# Sheet.net
KiCad netlist of a schematic drawn in Altium Designer
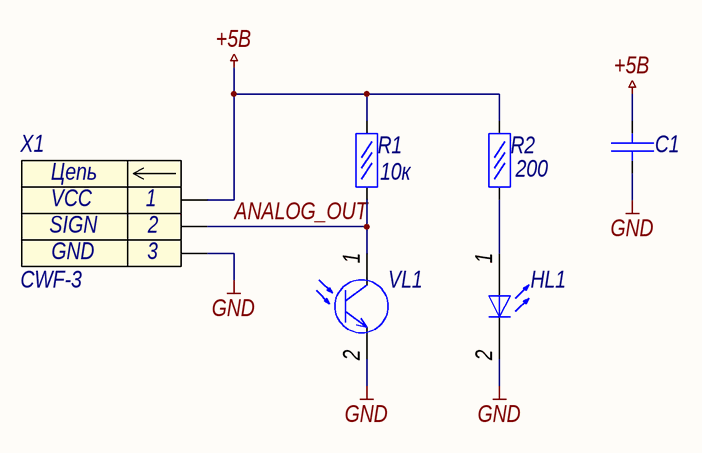
[diagram p0: Sheet.SchDoc]

(export (version "E")
  (design (tool "Eeschema 10.0.6"))
  (components
    (comp (ref "C1")
      (value "~")
      (footprint "C0805_AA")
      (description "Конденсатор кер.")
      (libsource (lib "mylib") (part "Конденсатор кер."))
    )
    (comp (ref "HL1") (value "~") (footprint "PCBComponent_2") (libsource (lib "mylib") (part "IR LED")))
    (comp (ref "R1")
      (value "10к")
      (footprint "R1206")
      (description "Резистор 0,05Вт")
      (libsource (lib "mylib") (part "Резистор  0,05Вт"))
    )
    (comp (ref "R2")
      (value "200")
      (footprint "R1206")
      (description "Резистор 0,05Вт")
      (libsource (lib "mylib") (part "Резистор  0,05Вт"))
    )
    (comp (ref "VL1")
      (value "~")
      (footprint "PCBComponent_1")
      (libsource (lib "mylib") (part "phototransistor"))
    )
    (comp (ref "X1")
      (value "CWF-3")
      (footprint "CWF-3")
      (description "Разъем - 3 конт. вилка")
      (fields (field (name "NAME") "CWF-3"))
      (libsource (lib "mylib") (part "Header_3_plg"))
    )
  )
  (nets
    (net (code "1") (name "+5В") (class "Default")
      (node (ref "C1") (pin "1") (pinfunction "1_1") (pintype "passive"))
      (node (ref "R1") (pin "2") (pinfunction "2_2") (pintype "passive"))
      (node (ref "R2") (pin "2") (pinfunction "2_2") (pintype "passive"))
      (node (ref "X1") (pin "1") (pinfunction "1_1") (pintype "passive"))
    )
    (net (code "2") (name "/ANALOG_OUT") (class "Default")
      (node (ref "R1") (pin "1") (pinfunction "1_1") (pintype "passive"))
      (node (ref "VL1") (pin "1") (pinfunction "C_1") (pintype "passive"))
      (node (ref "X1") (pin "2") (pinfunction "2_2") (pintype "passive"))
    )
    (net (code "3") (name "GND") (class "Default")
      (node (ref "C1") (pin "2") (pinfunction "2_2") (pintype "passive"))
      (node (ref "HL1") (pin "2") (pinfunction "K_2") (pintype "passive"))
      (node (ref "VL1") (pin "2") (pinfunction "E_2") (pintype "passive"))
      (node (ref "X1") (pin "3") (pinfunction "3_3") (pintype "passive"))
    )
    (net (code "4") (name "Net-(HL1-A)") (class "Default")
      (node (ref "HL1") (pin "1") (pinfunction "A_1") (pintype "passive"))
      (node (ref "R2") (pin "1") (pinfunction "1_1") (pintype "passive"))
    )
  )
)
